# simple-hat.net
KiCad netlist of a schematic drawn in EAGLE
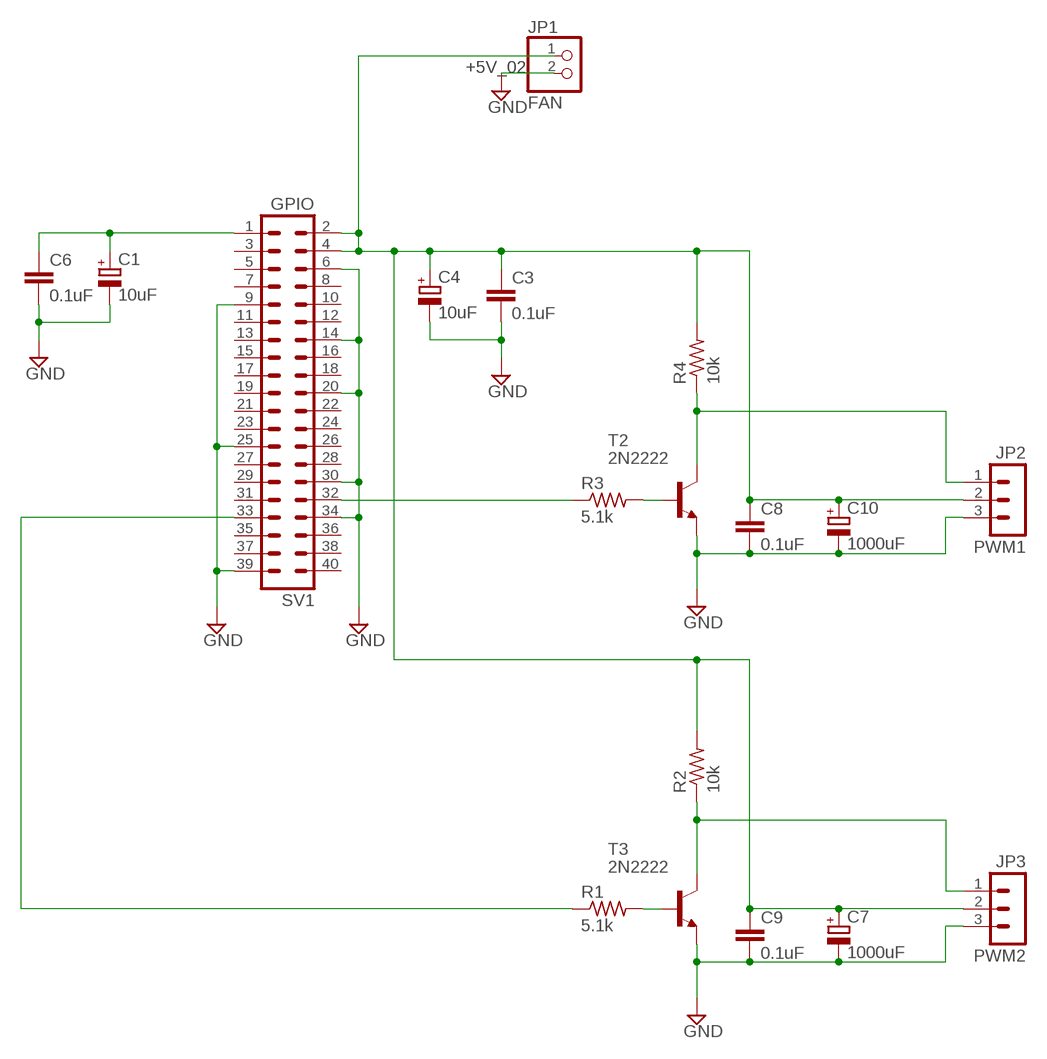
[diagram p0: schematic, sheet 1]

(export (version "E")
  (design (tool "Eeschema 10.0.6"))
  (components
    (comp (ref "C1")
      (value "10uF")
      (footprint "eagle-import:E2-5")
      (libsource (lib "eagle-import") (part "CPOL-EUE2-5"))
    )
    (comp (ref "C3")
      (value "0.1uF")
      (footprint "eagle-import:C025-025X050")
      (libsource (lib "eagle-import") (part "C-EU025-025X050"))
    )
    (comp (ref "C4")
      (value "10uF")
      (footprint "eagle-import:E2-5")
      (libsource (lib "eagle-import") (part "CPOL-EUE2-5"))
    )
    (comp (ref "C6")
      (value "0.1uF")
      (footprint "eagle-import:C025-025X050")
      (libsource (lib "eagle-import") (part "C-EU025-025X050"))
    )
    (comp (ref "C7")
      (value "1000uF")
      (footprint "eagle-import:E5-10,5")
      (libsource (lib "eagle-import") (part "CPOL-EUE5-10.5"))
    )
    (comp (ref "C8")
      (value "0.1uF")
      (footprint "eagle-import:C025-025X050")
      (libsource (lib "eagle-import") (part "C-EU025-025X050"))
    )
    (comp (ref "C9")
      (value "0.1uF")
      (footprint "eagle-import:C025-025X050")
      (libsource (lib "eagle-import") (part "C-EU025-025X050"))
    )
    (comp (ref "C10")
      (value "1000uF")
      (footprint "eagle-import:E5-10,5")
      (libsource (lib "eagle-import") (part "CPOL-EUE5-10.5"))
    )
    (comp (ref "JP1")
      (value "FAN")
      (footprint "eagle-import:1X02")
      (libsource (lib "eagle-import") (part "PINHD-1X2"))
    )
    (comp (ref "PWM1")
      (value "JP2")
      (footprint "eagle-import:MA03-1")
      (libsource (lib "eagle-import") (part "MA03-1"))
    )
    (comp (ref "PWM2")
      (value "JP3")
      (footprint "eagle-import:MA03-1")
      (libsource (lib "eagle-import") (part "MA03-1"))
    )
    (comp (ref "R1")
      (value "5.1k")
      (footprint "eagle-import:0207_7")
      (libsource (lib "eagle-import") (part "R-US_0207/7"))
    )
    (comp (ref "R2")
      (value "10k")
      (footprint "eagle-import:0207_7")
      (libsource (lib "eagle-import") (part "R-US_0207/7"))
    )
    (comp (ref "R3")
      (value "5.1k")
      (footprint "eagle-import:0207_7")
      (libsource (lib "eagle-import") (part "R-US_0207/7"))
    )
    (comp (ref "R4")
      (value "10k")
      (footprint "eagle-import:0207_7")
      (libsource (lib "eagle-import") (part "R-US_0207/7"))
    )
    (comp (ref "SV1")
      (value "GPIO")
      (footprint "eagle-import:MA20-2")
      (libsource (lib "eagle-import") (part "MA20-2"))
    )
    (comp (ref "T2")
      (value "2N2222")
      (footprint "eagle-import:TO92-EBC")
      (libsource (lib "eagle-import") (part "-NPN-TO92-EBC"))
    )
    (comp (ref "T3")
      (value "2N2222")
      (footprint "eagle-import:TO92-EBC")
      (libsource (lib "eagle-import") (part "-NPN-TO92-EBC"))
    )
  )
  (nets
    (net (code "1") (name "/+5V_02") (class "Default")
      (node (ref "C10") (pin "+") (pinfunction "+_+") (pintype "passive"))
      (node (ref "C3") (pin "1") (pinfunction "1_1") (pintype "passive"))
      (node (ref "C4") (pin "+") (pinfunction "+_+") (pintype "passive"))
      (node (ref "C7") (pin "+") (pinfunction "+_+") (pintype "passive"))
      (node (ref "C8") (pin "1") (pinfunction "1_1") (pintype "passive"))
      (node (ref "C9") (pin "1") (pinfunction "1_1") (pintype "passive"))
      (node (ref "JP1") (pin "1") (pinfunction "1_1") (pintype "passive"))
      (node (ref "PWM1") (pin "2") (pinfunction "2_2") (pintype "passive"))
      (node (ref "PWM2") (pin "2") (pinfunction "2_2") (pintype "passive"))
      (node (ref "R2") (pin "2") (pinfunction "2_2") (pintype "passive"))
      (node (ref "R4") (pin "2") (pinfunction "2_2") (pintype "passive"))
      (node (ref "SV1") (pin "2") (pinfunction "2_2") (pintype "passive"))
      (node (ref "SV1") (pin "4") (pinfunction "4_4") (pintype "passive"))
    )
    (net (code "2") (name "GND") (class "Default")
      (node (ref "C1") (pin "-") (pinfunction "-_-") (pintype "passive"))
      (node (ref "C10") (pin "-") (pinfunction "-_-") (pintype "passive"))
      (node (ref "C3") (pin "2") (pinfunction "2_2") (pintype "passive"))
      (node (ref "C4") (pin "-") (pinfunction "-_-") (pintype "passive"))
      (node (ref "C6") (pin "2") (pinfunction "2_2") (pintype "passive"))
      (node (ref "C7") (pin "-") (pinfunction "-_-") (pintype "passive"))
      (node (ref "C8") (pin "2") (pinfunction "2_2") (pintype "passive"))
      (node (ref "C9") (pin "2") (pinfunction "2_2") (pintype "passive"))
      (node (ref "JP1") (pin "2") (pinfunction "2_2") (pintype "passive"))
      (node (ref "PWM1") (pin "3") (pinfunction "3_3") (pintype "passive"))
      (node (ref "PWM2") (pin "3") (pinfunction "3_3") (pintype "passive"))
      (node (ref "SV1") (pin "14") (pinfunction "14_14") (pintype "passive"))
      (node (ref "SV1") (pin "20") (pinfunction "20_20") (pintype "passive"))
      (node (ref "SV1") (pin "25") (pinfunction "25_25") (pintype "passive"))
      (node (ref "SV1") (pin "30") (pinfunction "30_30") (pintype "passive"))
      (node (ref "SV1") (pin "34") (pinfunction "34_34") (pintype "passive"))
      (node (ref "SV1") (pin "39") (pinfunction "39_39") (pintype "passive"))
      (node (ref "SV1") (pin "6") (pinfunction "6_6") (pintype "passive"))
      (node (ref "SV1") (pin "9") (pinfunction "9_9") (pintype "passive"))
      (node (ref "T2") (pin "E") (pinfunction "E_E") (pintype "passive"))
      (node (ref "T3") (pin "E") (pinfunction "E_E") (pintype "passive"))
    )
    (net (code "3") (name "Net-(C1-Pad+)") (class "Default")
      (node (ref "C1") (pin "+") (pinfunction "+_+") (pintype "passive"))
      (node (ref "C6") (pin "1") (pinfunction "1_1") (pintype "passive"))
      (node (ref "SV1") (pin "1") (pinfunction "1_1") (pintype "passive"))
    )
    (net (code "4") (name "Net-(PWM1-Pad1)") (class "Default")
      (node (ref "PWM1") (pin "1") (pinfunction "1_1") (pintype "passive"))
      (node (ref "R4") (pin "1") (pinfunction "1_1") (pintype "passive"))
      (node (ref "T2") (pin "C") (pinfunction "C_C") (pintype "passive"))
    )
    (net (code "5") (name "Net-(PWM2-Pad1)") (class "Default")
      (node (ref "PWM2") (pin "1") (pinfunction "1_1") (pintype "passive"))
      (node (ref "R2") (pin "1") (pinfunction "1_1") (pintype "passive"))
      (node (ref "T3") (pin "C") (pinfunction "C_C") (pintype "passive"))
    )
    (net (code "6") (name "Net-(R1-Pad1)") (class "Default")
      (node (ref "R1") (pin "1") (pinfunction "1_1") (pintype "passive"))
      (node (ref "SV1") (pin "33") (pinfunction "33_33") (pintype "passive"))
    )
    (net (code "7") (name "Net-(R1-Pad2)") (class "Default")
      (node (ref "R1") (pin "2") (pinfunction "2_2") (pintype "passive"))
      (node (ref "T3") (pin "B") (pinfunction "B_B") (pintype "passive"))
    )
    (net (code "8") (name "Net-(R3-Pad1)") (class "Default")
      (node (ref "R3") (pin "1") (pinfunction "1_1") (pintype "passive"))
      (node (ref "SV1") (pin "32") (pinfunction "32_32") (pintype "passive"))
    )
    (net (code "9") (name "Net-(R3-Pad2)") (class "Default")
      (node (ref "R3") (pin "2") (pinfunction "2_2") (pintype "passive"))
      (node (ref "T2") (pin "B") (pinfunction "B_B") (pintype "passive"))
    )
    (net (code "10") (name "unconnected-(SV1-Pad3)") (class "Default")
      (node (ref "SV1") (pin "3") (pinfunction "3_3") (pintype "passive"))
    )
    (net (code "11") (name "unconnected-(SV1-Pad5)") (class "Default")
      (node (ref "SV1") (pin "5") (pinfunction "5_5") (pintype "passive"))
    )
    (net (code "12") (name "unconnected-(SV1-Pad7)") (class "Default")
      (node (ref "SV1") (pin "7") (pinfunction "7_7") (pintype "passive"))
    )
    (net (code "13") (name "unconnected-(SV1-Pad8)") (class "Default")
      (node (ref "SV1") (pin "8") (pinfunction "8_8") (pintype "passive"))
    )
    (net (code "14") (name "unconnected-(SV1-Pad10)") (class "Default")
      (node (ref "SV1") (pin "10") (pinfunction "10_10") (pintype "passive"))
    )
    (net (code "15") (name "unconnected-(SV1-Pad11)") (class "Default")
      (node (ref "SV1") (pin "11") (pinfunction "11_11") (pintype "passive"))
    )
    (net (code "16") (name "unconnected-(SV1-Pad12)") (class "Default")
      (node (ref "SV1") (pin "12") (pinfunction "12_12") (pintype "passive"))
    )
    (net (code "17") (name "unconnected-(SV1-Pad13)") (class "Default")
      (node (ref "SV1") (pin "13") (pinfunction "13_13") (pintype "passive"))
    )
    (net (code "18") (name "unconnected-(SV1-Pad15)") (class "Default")
      (node (ref "SV1") (pin "15") (pinfunction "15_15") (pintype "passive"))
    )
    (net (code "19") (name "unconnected-(SV1-Pad16)") (class "Default")
      (node (ref "SV1") (pin "16") (pinfunction "16_16") (pintype "passive"))
    )
    (net (code "20") (name "unconnected-(SV1-Pad17)") (class "Default")
      (node (ref "SV1") (pin "17") (pinfunction "17_17") (pintype "passive"))
    )
    (net (code "21") (name "unconnected-(SV1-Pad18)") (class "Default")
      (node (ref "SV1") (pin "18") (pinfunction "18_18") (pintype "passive"))
    )
    (net (code "22") (name "unconnected-(SV1-Pad19)") (class "Default")
      (node (ref "SV1") (pin "19") (pinfunction "19_19") (pintype "passive"))
    )
    (net (code "23") (name "unconnected-(SV1-Pad21)") (class "Default")
      (node (ref "SV1") (pin "21") (pinfunction "21_21") (pintype "passive"))
    )
    (net (code "24") (name "unconnected-(SV1-Pad22)") (class "Default")
      (node (ref "SV1") (pin "22") (pinfunction "22_22") (pintype "passive"))
    )
    (net (code "25") (name "unconnected-(SV1-Pad23)") (class "Default")
      (node (ref "SV1") (pin "23") (pinfunction "23_23") (pintype "passive"))
    )
    (net (code "26") (name "unconnected-(SV1-Pad24)") (class "Default")
      (node (ref "SV1") (pin "24") (pinfunction "24_24") (pintype "passive"))
    )
    (net (code "27") (name "unconnected-(SV1-Pad26)") (class "Default")
      (node (ref "SV1") (pin "26") (pinfunction "26_26") (pintype "passive"))
    )
    (net (code "28") (name "unconnected-(SV1-Pad27)") (class "Default")
      (node (ref "SV1") (pin "27") (pinfunction "27_27") (pintype "passive"))
    )
    (net (code "29") (name "unconnected-(SV1-Pad28)") (class "Default")
      (node (ref "SV1") (pin "28") (pinfunction "28_28") (pintype "passive"))
    )
    (net (code "30") (name "unconnected-(SV1-Pad29)") (class "Default")
      (node (ref "SV1") (pin "29") (pinfunction "29_29") (pintype "passive"))
    )
    (net (code "31") (name "unconnected-(SV1-Pad31)") (class "Default")
      (node (ref "SV1") (pin "31") (pinfunction "31_31") (pintype "passive"))
    )
    (net (code "32") (name "unconnected-(SV1-Pad35)") (class "Default")
      (node (ref "SV1") (pin "35") (pinfunction "35_35") (pintype "passive"))
    )
    (net (code "33") (name "unconnected-(SV1-Pad36)") (class "Default")
      (node (ref "SV1") (pin "36") (pinfunction "36_36") (pintype "passive"))
    )
    (net (code "34") (name "unconnected-(SV1-Pad37)") (class "Default")
      (node (ref "SV1") (pin "37") (pinfunction "37_37") (pintype "passive"))
    )
    (net (code "35") (name "unconnected-(SV1-Pad38)") (class "Default")
      (node (ref "SV1") (pin "38") (pinfunction "38_38") (pintype "passive"))
    )
    (net (code "36") (name "unconnected-(SV1-Pad40)") (class "Default")
      (node (ref "SV1") (pin "40") (pinfunction "40_40") (pintype "passive"))
    )
  )
)
